# metro_mini_irRemote.net
KiCad netlist of a schematic drawn in EAGLE
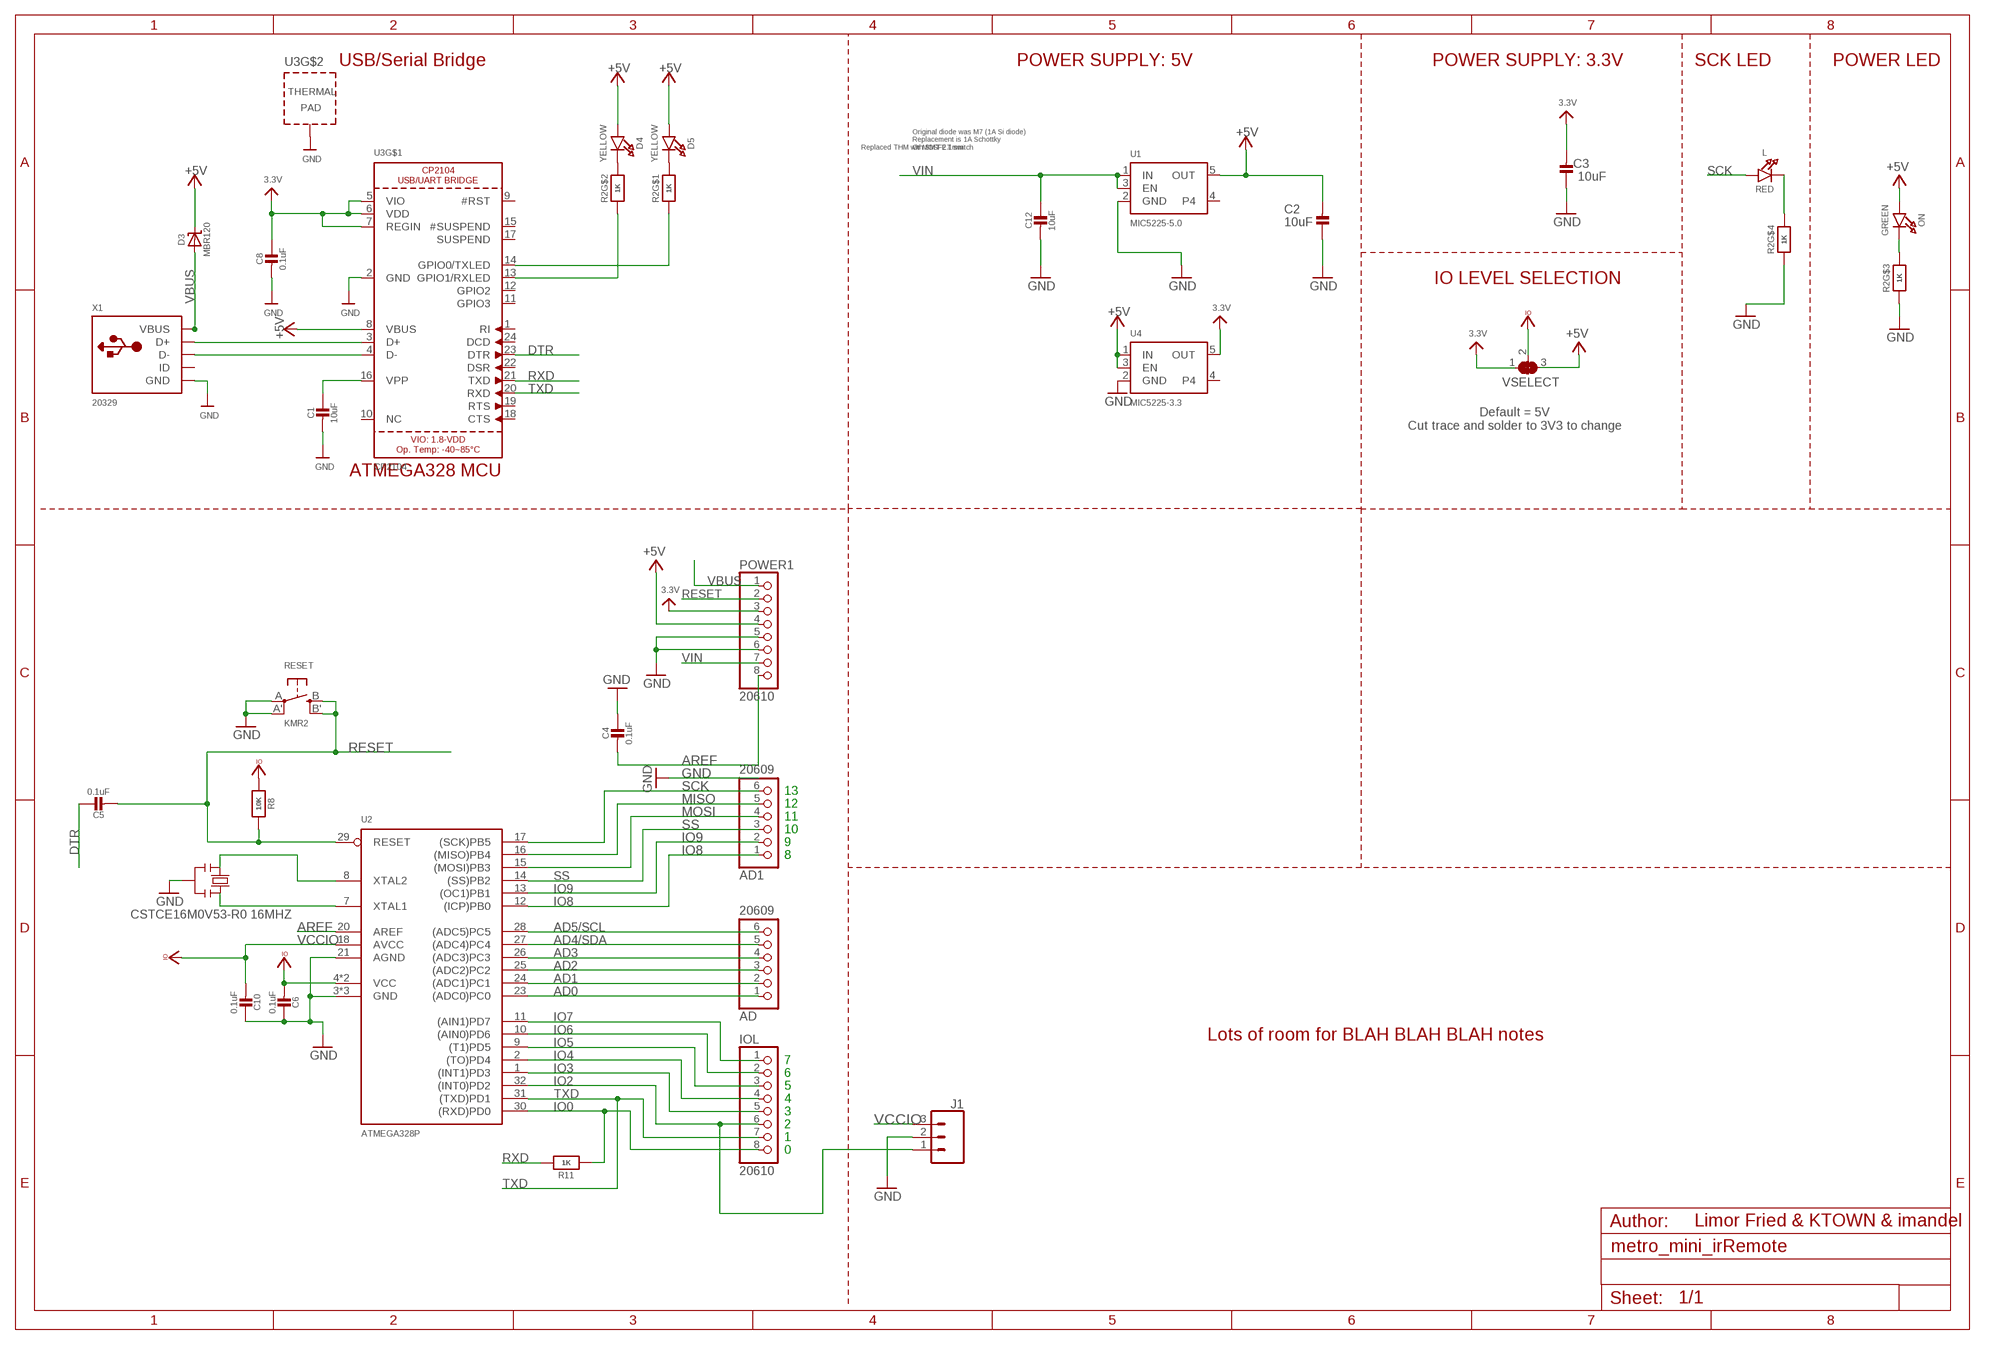
[diagram p0: schematic, sheet 1]

(export (version "E")
  (design (tool "Eeschema 10.0.6"))
  (components
    (comp (ref "AD")
      (value "20609")
      (footprint "eagle-import:1X06_ROUND")
      (libsource (lib "eagle-import") (part "HEADER-1X6ROUND"))
    )
    (comp (ref "AD1")
      (value "20609")
      (footprint "eagle-import:1X06_ROUND")
      (libsource (lib "eagle-import") (part "HEADER-1X6ROUND"))
    )
    (comp (ref "C1")
      (value "10uF")
      (footprint "eagle-import:0805-NO")
      (libsource (lib "eagle-import") (part "CAP_CERAMIC0805-NOOUTLINE"))
    )
    (comp (ref "C2")
      (value "10uF")
      (footprint "eagle-import:0805-NO")
      (libsource (lib "eagle-import") (part "CAP_CERAMIC0805-NOOUTLINE"))
    )
    (comp (ref "C3")
      (value "10uF")
      (footprint "eagle-import:0805-NO")
      (libsource (lib "eagle-import") (part "CAP_CERAMIC0805-NOOUTLINE"))
    )
    (comp (ref "C4")
      (value "0.1uF")
      (footprint "eagle-import:0805-NO")
      (libsource (lib "eagle-import") (part "CAP_CERAMIC0805-NOOUTLINE"))
    )
    (comp (ref "C5")
      (value "0.1uF")
      (footprint "eagle-import:_0805MP")
      (libsource (lib "eagle-import") (part "CAP_CERAMIC_0805MP"))
    )
    (comp (ref "C6")
      (value "0.1uF")
      (footprint "eagle-import:0805-NO")
      (libsource (lib "eagle-import") (part "CAP_CERAMIC0805-NOOUTLINE"))
    )
    (comp (ref "C8")
      (value "0.1uF")
      (footprint "eagle-import:0805-NO")
      (libsource (lib "eagle-import") (part "CAP_CERAMIC0805-NOOUTLINE"))
    )
    (comp (ref "C10")
      (value "0.1uF")
      (footprint "eagle-import:0805-NO")
      (libsource (lib "eagle-import") (part "CAP_CERAMIC0805-NOOUTLINE"))
    )
    (comp (ref "C12")
      (value "10uF")
      (footprint "eagle-import:0805-NO")
      (libsource (lib "eagle-import") (part "CAP_CERAMIC0805-NOOUTLINE"))
    )
    (comp (ref "D3")
      (value "MBR120")
      (footprint "eagle-import:SOD-123")
      (libsource (lib "eagle-import") (part "DIODE-SCHOTTKYSOD-123"))
    )
    (comp (ref "D4")
      (value "YELLOW")
      (footprint "eagle-import:CHIPLED_0805_NOOUTLINE")
      (libsource (lib "eagle-import") (part "LED0805_NOOUTLINE"))
    )
    (comp (ref "D5")
      (value "YELLOW")
      (footprint "eagle-import:CHIPLED_0805_NOOUTLINE")
      (libsource (lib "eagle-import") (part "LED0805_NOOUTLINE"))
    )
    (comp (ref "IOL")
      (value "20610")
      (footprint "eagle-import:1X08_ROUND")
      (libsource (lib "eagle-import") (part "HEADER-1X8ROUND"))
    )
    (comp (ref "J1")
      (value "CONN_03")
      (footprint "eagle-import:1X03")
      (libsource (lib "eagle-import") (part "CONN_03"))
    )
    (comp (ref "L")
      (value "RED")
      (footprint "eagle-import:CHIPLED_0805_NOOUTLINE")
      (libsource (lib "eagle-import") (part "LED0805_NOOUTLINE"))
    )
    (comp (ref "ON")
      (value "GREEN")
      (footprint "eagle-import:CHIPLED_0805_NOOUTLINE")
      (libsource (lib "eagle-import") (part "LED0805_NOOUTLINE"))
    )
    (comp (ref "POWER1")
      (value "20610")
      (footprint "eagle-import:1X08_ROUND_70")
      (libsource (lib "eagle-import") (part "HEADER-1X870MIL"))
    )
    (comp (ref "R2")
      (value "1K")
      (footprint "eagle-import:RESPACK_4X0603")
      (libsource (lib "eagle-import") (part "RESISTOR_4PACK"))
    )
    (comp (ref "R8")
      (value "10K")
      (footprint "eagle-import:0805-NO")
      (libsource (lib "eagle-import") (part "RESISTOR0805_NOOUTLINE"))
    )
    (comp (ref "R11")
      (value "1K")
      (footprint "eagle-import:0805-NO")
      (libsource (lib "eagle-import") (part "RESISTOR0805_NOOUTLINE"))
    )
    (comp (ref "RESET")
      (value "KMR2")
      (footprint "eagle-import:BTN_KMR2_4.6X2.8")
      (libsource (lib "eagle-import") (part "SWITCH_TACT_SMT4.6X2.8"))
    )
    (comp (ref "U1")
      (value "MIC5225-5.0")
      (footprint "eagle-import:SOT23-5")
      (libsource (lib "eagle-import") (part "VREG_SOT23-5"))
    )
    (comp (ref "U2")
      (value "ATMEGA328P")
      (footprint "eagle-import:MLF32-TH")
      (libsource (lib "eagle-import") (part "ATMEGA328P"))
    )
    (comp (ref "U3")
      (value "CP2104")
      (footprint "eagle-import:QFN24_4MM_SMSC")
      (libsource (lib "eagle-import") (part "CP2104"))
    )
    (comp (ref "U4")
      (value "MIC5225-3.3")
      (footprint "eagle-import:SOT23-5")
      (libsource (lib "eagle-import") (part "VREG_SOT23-5"))
    )
    (comp (ref "VSELECT")
      (value "SOLDERJUMPER_2WAY")
      (footprint "eagle-import:SOLDERJUMPER_2WAY_OPEN_NOPASTE")
      (libsource (lib "eagle-import") (part "SOLDERJUMPER_2WAY"))
    )
    (comp (ref "X1")
      (value "20329")
      (footprint "eagle-import:4UCONN_20329_V2")
      (libsource (lib "eagle-import") (part "USB_MICRO_20329_V2"))
    )
    (comp (ref "Y2")
      (value "CSTCE16M0V53-R0 16MHZ")
      (footprint "eagle-import:RESONATOR")
      (libsource (lib "eagle-import") (part "RESONATORMU"))
    )
  )
  (nets
    (net (code "1") (name "+5V") (class "Default")
      (node (ref "C2") (pin "2") (pinfunction "2_2") (pintype "passive"))
      (node (ref "D3") (pin "C") (pinfunction "C_C") (pintype "passive"))
      (node (ref "D4") (pin "A") (pinfunction "A_A") (pintype "passive"))
      (node (ref "D5") (pin "A") (pinfunction "A_A") (pintype "passive"))
      (node (ref "ON") (pin "A") (pinfunction "A_A") (pintype "passive"))
      (node (ref "POWER1") (pin "4") (pinfunction "4_4") (pintype "passive"))
      (node (ref "U1") (pin "5") (pinfunction "OUT_5") (pintype "power_in"))
      (node (ref "U3") (pin "8") (pinfunction "VBUS_8") (pintype "power_in"))
      (node (ref "U4") (pin "1") (pinfunction "IN_1") (pintype "power_in"))
      (node (ref "U4") (pin "3") (pinfunction "EN_3") (pintype "input"))
      (node (ref "VSELECT") (pin "3") (pinfunction "3_3") (pintype "passive"))
    )
    (net (code "2") (name "/AD0") (class "Default")
      (node (ref "AD") (pin "1") (pinfunction "1_1") (pintype "passive"))
      (node (ref "U2") (pin "23") (pinfunction "(ADC0)PC0_23") (pintype "bidirectional"))
    )
    (net (code "3") (name "/AD1") (class "Default")
      (node (ref "AD") (pin "2") (pinfunction "2_2") (pintype "passive"))
      (node (ref "U2") (pin "24") (pinfunction "(ADC1)PC1_24") (pintype "bidirectional"))
    )
    (net (code "4") (name "/AD2") (class "Default")
      (node (ref "AD") (pin "3") (pinfunction "3_3") (pintype "passive"))
      (node (ref "U2") (pin "25") (pinfunction "(ADC2)PC2_25") (pintype "bidirectional"))
    )
    (net (code "5") (name "/AD3") (class "Default")
      (node (ref "AD") (pin "4") (pinfunction "4_4") (pintype "passive"))
      (node (ref "U2") (pin "26") (pinfunction "(ADC3)PC3_26") (pintype "bidirectional"))
    )
    (net (code "6") (name "/AD4{slash}SDA") (class "Default")
      (node (ref "AD") (pin "5") (pinfunction "5_5") (pintype "passive"))
      (node (ref "U2") (pin "27") (pinfunction "(ADC4)PC4_27") (pintype "bidirectional"))
    )
    (net (code "7") (name "/AD5{slash}SCL") (class "Default")
      (node (ref "AD") (pin "6") (pinfunction "6_6") (pintype "passive"))
      (node (ref "U2") (pin "28") (pinfunction "(ADC5)PC5_28") (pintype "bidirectional"))
    )
    (net (code "8") (name "/AREF") (class "Default")
      (node (ref "C4") (pin "2") (pinfunction "2_2") (pintype "passive"))
      (node (ref "POWER1") (pin "8") (pinfunction "8_8") (pintype "passive"))
      (node (ref "U2") (pin "20") (pinfunction "AREF_20") (pintype "power_in"))
    )
    (net (code "9") (name "/DTR") (class "Default")
      (node (ref "C5") (pin "1") (pinfunction "1_1") (pintype "passive"))
      (node (ref "U3") (pin "23") (pinfunction "DTR_23") (pintype "output"))
    )
    (net (code "10") (name "/IO0") (class "Default")
      (node (ref "IOL") (pin "8") (pinfunction "8_8") (pintype "passive"))
      (node (ref "R11") (pin "1") (pinfunction "1_1") (pintype "passive"))
      (node (ref "U2") (pin "30") (pinfunction "(RXD)PD0_30") (pintype "bidirectional"))
    )
    (net (code "11") (name "/IO2") (class "Default")
      (node (ref "IOL") (pin "6") (pinfunction "6_6") (pintype "passive"))
      (node (ref "J1") (pin "1") (pinfunction "1_1") (pintype "passive"))
      (node (ref "U2") (pin "32") (pinfunction "(INT0)PD2_32") (pintype "bidirectional"))
    )
    (net (code "12") (name "/IO3") (class "Default")
      (node (ref "IOL") (pin "5") (pinfunction "5_5") (pintype "passive"))
      (node (ref "U2") (pin "1") (pinfunction "(INT1)PD3_1") (pintype "bidirectional"))
    )
    (net (code "13") (name "/IO4") (class "Default")
      (node (ref "IOL") (pin "4") (pinfunction "4_4") (pintype "passive"))
      (node (ref "U2") (pin "2") (pinfunction "(TO)PD4_2") (pintype "bidirectional"))
    )
    (net (code "14") (name "/IO5") (class "Default")
      (node (ref "IOL") (pin "3") (pinfunction "3_3") (pintype "passive"))
      (node (ref "U2") (pin "9") (pinfunction "(T1)PD5_9") (pintype "bidirectional"))
    )
    (net (code "15") (name "/IO6") (class "Default")
      (node (ref "IOL") (pin "2") (pinfunction "2_2") (pintype "passive"))
      (node (ref "U2") (pin "10") (pinfunction "(AIN0)PD6_10") (pintype "bidirectional"))
    )
    (net (code "16") (name "/IO7") (class "Default")
      (node (ref "IOL") (pin "1") (pinfunction "1_1") (pintype "passive"))
      (node (ref "U2") (pin "11") (pinfunction "(AIN1)PD7_11") (pintype "bidirectional"))
    )
    (net (code "17") (name "/IO8") (class "Default")
      (node (ref "AD1") (pin "1") (pinfunction "1_1") (pintype "passive"))
      (node (ref "U2") (pin "12") (pinfunction "(ICP)PB0_12") (pintype "bidirectional"))
    )
    (net (code "18") (name "/IO9") (class "Default")
      (node (ref "AD1") (pin "2") (pinfunction "2_2") (pintype "passive"))
      (node (ref "U2") (pin "13") (pinfunction "(OC1)PB1_13") (pintype "bidirectional"))
    )
    (net (code "19") (name "/MISO") (class "Default")
      (node (ref "AD1") (pin "5") (pinfunction "5_5") (pintype "passive"))
      (node (ref "U2") (pin "16") (pinfunction "(MISO)PB4_16") (pintype "bidirectional"))
    )
    (net (code "20") (name "/MOSI") (class "Default")
      (node (ref "AD1") (pin "4") (pinfunction "4_4") (pintype "passive"))
      (node (ref "U2") (pin "15") (pinfunction "(MOSI)PB3_15") (pintype "bidirectional"))
    )
    (net (code "21") (name "/RESET") (class "Default")
      (node (ref "C5") (pin "2") (pinfunction "2_2") (pintype "passive"))
      (node (ref "POWER1") (pin "2") (pinfunction "2_2") (pintype "passive"))
      (node (ref "R8") (pin "1") (pinfunction "1_1") (pintype "passive"))
      (node (ref "RESET") (pin "B") (pinfunction "S_B") (pintype "passive"))
      (node (ref "RESET") (pin "B'") (pinfunction "S1_B'") (pintype "passive"))
      (node (ref "U2") (pin "29") (pinfunction "RESET_29") (pintype "bidirectional"))
    )
    (net (code "22") (name "/RXD") (class "Default")
      (node (ref "R11") (pin "2") (pinfunction "2_2") (pintype "passive"))
      (node (ref "U3") (pin "21") (pinfunction "TXD_21") (pintype "output"))
    )
    (net (code "23") (name "/SCK") (class "Default")
      (node (ref "AD1") (pin "6") (pinfunction "6_6") (pintype "passive"))
      (node (ref "L") (pin "A") (pinfunction "A_A") (pintype "passive"))
      (node (ref "U2") (pin "17") (pinfunction "(SCK)PB5_17") (pintype "bidirectional"))
    )
    (net (code "24") (name "/SS") (class "Default")
      (node (ref "AD1") (pin "3") (pinfunction "3_3") (pintype "passive"))
      (node (ref "U2") (pin "14") (pinfunction "(SS)PB2_14") (pintype "bidirectional"))
    )
    (net (code "25") (name "/TXD") (class "Default")
      (node (ref "IOL") (pin "7") (pinfunction "7_7") (pintype "passive"))
      (node (ref "U2") (pin "31") (pinfunction "(TXD)PD1_31") (pintype "bidirectional"))
      (node (ref "U3") (pin "20") (pinfunction "RXD_20") (pintype "input"))
    )
    (net (code "26") (name "/VBUS") (class "Default")
      (node (ref "D3") (pin "A") (pinfunction "A_A") (pintype "passive"))
      (node (ref "POWER1") (pin "1") (pinfunction "1_1") (pintype "passive"))
      (node (ref "X1") (pin "VBUS") (pinfunction "VBUS_VBUS") (pintype "power_in"))
    )
    (net (code "27") (name "/VIN") (class "Default")
      (node (ref "C12") (pin "1") (pinfunction "1_1") (pintype "passive"))
      (node (ref "POWER1") (pin "7") (pinfunction "7_7") (pintype "passive"))
      (node (ref "U1") (pin "1") (pinfunction "IN_1") (pintype "power_in"))
      (node (ref "U1") (pin "3") (pinfunction "EN_3") (pintype "input"))
    )
    (net (code "28") (name "3.3V") (class "Default")
      (node (ref "C3") (pin "2") (pinfunction "2_2") (pintype "passive"))
      (node (ref "C8") (pin "1") (pinfunction "1_1") (pintype "passive"))
      (node (ref "POWER1") (pin "3") (pinfunction "3_3") (pintype "passive"))
      (node (ref "U3") (pin "5") (pinfunction "VIO_5") (pintype "power_in"))
      (node (ref "U3") (pin "6") (pinfunction "VDD_6") (pintype "power_in"))
      (node (ref "U3") (pin "7") (pinfunction "REGIN_7") (pintype "power_in"))
      (node (ref "U4") (pin "5") (pinfunction "OUT_5") (pintype "power_in"))
      (node (ref "VSELECT") (pin "1") (pinfunction "1_1") (pintype "passive"))
    )
    (net (code "29") (name "GND") (class "Default")
      (node (ref "C1") (pin "2") (pinfunction "2_2") (pintype "passive"))
      (node (ref "C10") (pin "1") (pinfunction "1_1") (pintype "passive"))
      (node (ref "C12") (pin "2") (pinfunction "2_2") (pintype "passive"))
      (node (ref "C2") (pin "1") (pinfunction "1_1") (pintype "passive"))
      (node (ref "C3") (pin "1") (pinfunction "1_1") (pintype "passive"))
      (node (ref "C4") (pin "1") (pinfunction "1_1") (pintype "passive"))
      (node (ref "C6") (pin "1") (pinfunction "1_1") (pintype "passive"))
      (node (ref "C8") (pin "2") (pinfunction "2_2") (pintype "passive"))
      (node (ref "J1") (pin "2") (pinfunction "2_2") (pintype "passive"))
      (node (ref "POWER1") (pin "5") (pinfunction "5_5") (pintype "passive"))
      (node (ref "POWER1") (pin "6") (pinfunction "6_6") (pintype "passive"))
      (node (ref "R2") (pin "3") (pinfunction "1_3") (pintype "passive"))
      (node (ref "R2") (pin "4") (pinfunction "1_4") (pintype "passive"))
      (node (ref "RESET") (pin "A") (pinfunction "P_A") (pintype "passive"))
      (node (ref "RESET") (pin "A'") (pinfunction "P1_A'") (pintype "passive"))
      (node (ref "U1") (pin "2") (pinfunction "GND_2") (pintype "power_in"))
      (node (ref "U2") (pin "21") (pinfunction "AGND_21") (pintype "power_in"))
      (node (ref "U2") (pin "3") (pinfunction "GND_3") (pintype "power_in"))
      (node (ref "U2") (pin "5") (pinfunction "GND_5") (pintype "power_in"))
      (node (ref "U2") (pin "TH") (pinfunction "GND_TH") (pintype "power_in"))
      (node (ref "U3") (pin "2") (pinfunction "GND_2") (pintype "power_in"))
      (node (ref "U3") (pin "THERM") (pinfunction "TP_THERM") (pintype "power_in"))
      (node (ref "U4") (pin "2") (pinfunction "GND_2") (pintype "power_in"))
      (node (ref "X1") (pin "BASE@1") (pinfunction "GND_BASE@1") (pintype "power_in"))
      (node (ref "X1") (pin "BASE@2") (pinfunction "GND_BASE@2") (pintype "power_in"))
      (node (ref "X1") (pin "GND") (pinfunction "GND_GND") (pintype "power_in"))
      (node (ref "X1") (pin "SPRT@1") (pinfunction "GND_SPRT@1") (pintype "power_in"))
      (node (ref "X1") (pin "SPRT@2") (pinfunction "GND_SPRT@2") (pintype "power_in"))
      (node (ref "X1") (pin "SPRT@3") (pinfunction "GND_SPRT@3") (pintype "power_in"))
      (node (ref "X1") (pin "SPRT@4") (pinfunction "GND_SPRT@4") (pintype "power_in"))
      (node (ref "Y2") (pin "2") (pinfunction "2_2") (pintype "passive"))
    )
    (net (code "30") (name "Net-(R2A-2)") (class "Default")
      (node (ref "D5") (pin "C") (pinfunction "C_C") (pintype "passive"))
      (node (ref "R2") (pin "8") (pinfunction "2_8") (pintype "passive"))
    )
    (net (code "31") (name "Net-(R2B-1)") (class "Default")
      (node (ref "R2") (pin "2") (pinfunction "1_2") (pintype "passive"))
      (node (ref "U3") (pin "13") (pinfunction "GPIO1/RXLED_13") (pintype "bidirectional"))
    )
    (net (code "32") (name "Net-(R2B-2)") (class "Default")
      (node (ref "D4") (pin "C") (pinfunction "C_C") (pintype "passive"))
      (node (ref "R2") (pin "7") (pinfunction "2_7") (pintype "passive"))
    )
    (net (code "33") (name "Net-(R2C-2)") (class "Default")
      (node (ref "ON") (pin "C") (pinfunction "C_C") (pintype "passive"))
      (node (ref "R2") (pin "6") (pinfunction "2_6") (pintype "passive"))
    )
    (net (code "34") (name "Net-(R2D-2)") (class "Default")
      (node (ref "L") (pin "C") (pinfunction "C_C") (pintype "passive"))
      (node (ref "R2") (pin "5") (pinfunction "2_5") (pintype "passive"))
    )
    (net (code "35") (name "Net-(U2-XTAL1)") (class "Default")
      (node (ref "U2") (pin "7") (pinfunction "XTAL1_7") (pintype "bidirectional"))
      (node (ref "Y2") (pin "3") (pinfunction "3_3") (pintype "passive"))
    )
    (net (code "36") (name "Net-(U2-XTAL2)") (class "Default")
      (node (ref "U2") (pin "8") (pinfunction "XTAL2_8") (pintype "bidirectional"))
      (node (ref "Y2") (pin "1") (pinfunction "1_1") (pintype "passive"))
    )
    (net (code "37") (name "Net-(U3A-D+)") (class "Default")
      (node (ref "U3") (pin "3") (pinfunction "D+_3") (pintype "bidirectional"))
      (node (ref "X1") (pin "D+") (pinfunction "D+_D+") (pintype "bidirectional"))
    )
    (net (code "38") (name "Net-(U3A-D-)") (class "Default")
      (node (ref "U3") (pin "4") (pinfunction "D-_4") (pintype "bidirectional"))
      (node (ref "X1") (pin "D-") (pinfunction "D-_D-") (pintype "bidirectional"))
    )
    (net (code "39") (name "Net-(U3A-GPIO0{slash}TXLED)") (class "Default")
      (node (ref "R2") (pin "1") (pinfunction "1_1") (pintype "passive"))
      (node (ref "U3") (pin "14") (pinfunction "GPIO0/TXLED_14") (pintype "bidirectional"))
    )
    (net (code "40") (name "Net-(U3A-VPP)") (class "Default")
      (node (ref "C1") (pin "1") (pinfunction "1_1") (pintype "passive"))
      (node (ref "U3") (pin "16") (pinfunction "VPP_16") (pintype "bidirectional"))
    )
    (net (code "41") (name "VCCIO") (class "Default")
      (node (ref "C10") (pin "2") (pinfunction "2_2") (pintype "passive"))
      (node (ref "C6") (pin "2") (pinfunction "2_2") (pintype "passive"))
      (node (ref "J1") (pin "3") (pinfunction "3_3") (pintype "passive"))
      (node (ref "R8") (pin "2") (pinfunction "2_2") (pintype "passive"))
      (node (ref "U2") (pin "18") (pinfunction "AVCC_18") (pintype "power_in"))
      (node (ref "U2") (pin "4") (pinfunction "VCC_4") (pintype "power_in"))
      (node (ref "U2") (pin "6") (pinfunction "VCC_6") (pintype "power_in"))
      (node (ref "VSELECT") (pin "2") (pinfunction "2_2") (pintype "passive"))
    )
    (net (code "42") (name "unconnected-(U1-P4-Pad4)") (class "Default")
      (node (ref "U1") (pin "4") (pinfunction "P4_4") (pintype "bidirectional"))
    )
    (net (code "43") (name "unconnected-(U3A-#RST-Pad9)") (class "Default")
      (node (ref "U3") (pin "9") (pinfunction "#RST_9") (pintype "bidirectional"))
    )
    (net (code "44") (name "unconnected-(U3A-#SUSPEND-Pad15)") (class "Default")
      (node (ref "U3") (pin "15") (pinfunction "#SUSPEND_15") (pintype "output"))
    )
    (net (code "45") (name "unconnected-(U3A-CTS-Pad18)") (class "Default")
      (node (ref "U3") (pin "18") (pinfunction "CTS_18") (pintype "input"))
    )
    (net (code "46") (name "unconnected-(U3A-DCD-Pad24)") (class "Default")
      (node (ref "U3") (pin "24") (pinfunction "DCD_24") (pintype "input"))
    )
    (net (code "47") (name "unconnected-(U3A-DSR-Pad22)") (class "Default")
      (node (ref "U3") (pin "22") (pinfunction "DSR_22") (pintype "input"))
    )
    (net (code "48") (name "unconnected-(U3A-GPIO2-Pad12)") (class "Default")
      (node (ref "U3") (pin "12") (pinfunction "GPIO2_12") (pintype "bidirectional"))
    )
    (net (code "49") (name "unconnected-(U3A-GPIO3-Pad11)") (class "Default")
      (node (ref "U3") (pin "11") (pinfunction "GPIO3_11") (pintype "bidirectional"))
    )
    (net (code "50") (name "unconnected-(U3A-NC-Pad10)") (class "Default")
      (node (ref "U3") (pin "10") (pinfunction "NC_10") (pintype "no_connect"))
    )
    (net (code "51") (name "unconnected-(U3A-RI-Pad1)") (class "Default")
      (node (ref "U3") (pin "1") (pinfunction "RI_1") (pintype "input"))
    )
    (net (code "52") (name "unconnected-(U3A-RTS-Pad19)") (class "Default")
      (node (ref "U3") (pin "19") (pinfunction "RTS_19") (pintype "output"))
    )
    (net (code "53") (name "unconnected-(U3A-SUSPEND-Pad17)") (class "Default")
      (node (ref "U3") (pin "17") (pinfunction "SUSPEND_17") (pintype "output"))
    )
    (net (code "54") (name "unconnected-(U4-P4-Pad4)") (class "Default")
      (node (ref "U4") (pin "4") (pinfunction "P4_4") (pintype "bidirectional"))
    )
    (net (code "55") (name "unconnected-(X1-PadID)") (class "Default")
      (node (ref "X1") (pin "ID") (pinfunction "ID_ID") (pintype "bidirectional"))
    )
  )
)
